# Wallboxsteuerung-WEMOS-14062021.net
KiCad netlist of a schematic drawn in EAGLE
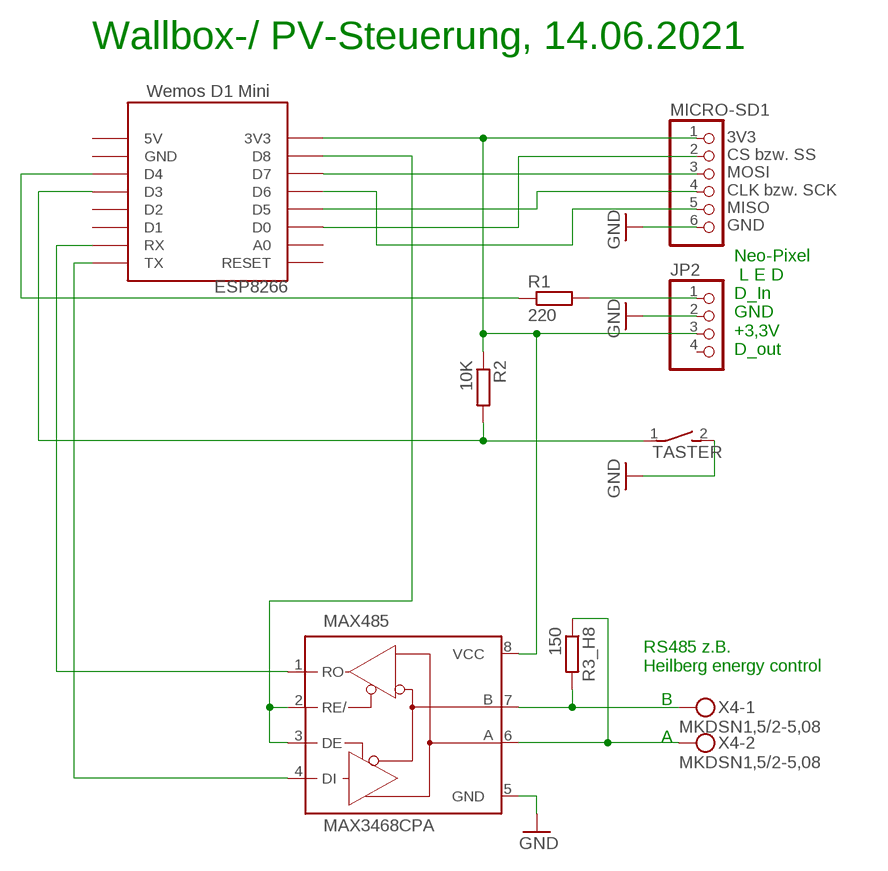
[diagram p0: schematic, sheet 1]

(export (version "E")
  (design (tool "Eeschema 10.0.6"))
  (components
    (comp (ref "ESP8266")
      (value "Wemos D1 Mini")
      (footprint "eagle-import:WEMOS-D1-MINI")
      (libsource (lib "eagle-import") (part "WEMOS-D1-MINI"))
    )
    (comp (ref "JP2")
      (value "PINHD-1X4")
      (footprint "eagle-import:1X04")
      (libsource (lib "eagle-import") (part "PINHD-1X4"))
    )
    (comp (ref "MAX485")
      (value "MAX3468CPA")
      (footprint "eagle-import:DIL08")
      (libsource (lib "eagle-import") (part "MAX34PA68C"))
    )
    (comp (ref "MICRO-SD1")
      (value "PINHD-1X6")
      (footprint "eagle-import:1X06")
      (libsource (lib "eagle-import") (part "PINHD-1X6"))
    )
    (comp (ref "R1")
      (value "220")
      (footprint "eagle-import:0309V")
      (libsource (lib "eagle-import") (part "R-EU_0309/V"))
    )
    (comp (ref "R2")
      (value "10K")
      (footprint "eagle-import:0309V")
      (libsource (lib "eagle-import") (part "R-EU_0309/V"))
    )
    (comp (ref "R3_H8")
      (value "150")
      (footprint "eagle-import:0309V")
      (libsource (lib "eagle-import") (part "R-EU_0309/V"))
    )
    (comp (ref "TASTER")
      (value "DS01E")
      (footprint "eagle-import:DS-01")
      (libsource (lib "eagle-import") (part "DS01E"))
    )
    (comp (ref "X4")
      (value "MKDSN1,5/2-5,08")
      (footprint "eagle-import:MKDSN1,5_2-5,08")
      (libsource (lib "eagle-import") (part "MKDSN1,5/2-5,08"))
    )
  )
  (nets
    (net (code "1") (name "GND") (class "Default")
      (node (ref "JP2") (pin "2") (pinfunction "2_2") (pintype "passive"))
      (node (ref "MAX485") (pin "5") (pinfunction "GND_5") (pintype "power_in"))
      (node (ref "MICRO-SD1") (pin "6") (pinfunction "6_6") (pintype "passive"))
      (node (ref "TASTER") (pin "2") (pinfunction "2_2") (pintype "passive"))
    )
    (net (code "2") (name "Net-(ESP8266-PadD0)") (class "Default")
      (node (ref "ESP8266") (pin "D0") (pinfunction "D0_D0") (pintype "bidirectional"))
      (node (ref "MICRO-SD1") (pin "2") (pinfunction "2_2") (pintype "passive"))
    )
    (net (code "3") (name "Net-(ESP8266-PadD3)") (class "Default")
      (node (ref "ESP8266") (pin "D3") (pinfunction "D3_D3") (pintype "bidirectional"))
      (node (ref "R2") (pin "2") (pinfunction "2_2") (pintype "passive"))
      (node (ref "TASTER") (pin "1") (pinfunction "1_1") (pintype "passive"))
    )
    (net (code "4") (name "Net-(ESP8266-PadD4)") (class "Default")
      (node (ref "ESP8266") (pin "D4") (pinfunction "D4_D4") (pintype "bidirectional"))
      (node (ref "R1") (pin "1") (pinfunction "1_1") (pintype "passive"))
    )
    (net (code "5") (name "Net-(ESP8266-PadD5)") (class "Default")
      (node (ref "ESP8266") (pin "D5") (pinfunction "D5_D5") (pintype "bidirectional"))
      (node (ref "MICRO-SD1") (pin "4") (pinfunction "4_4") (pintype "passive"))
    )
    (net (code "6") (name "Net-(ESP8266-PadD6)") (class "Default")
      (node (ref "ESP8266") (pin "D6") (pinfunction "D6_D6") (pintype "bidirectional"))
      (node (ref "MICRO-SD1") (pin "5") (pinfunction "5_5") (pintype "passive"))
    )
    (net (code "7") (name "Net-(ESP8266-PadD7)") (class "Default")
      (node (ref "ESP8266") (pin "D7") (pinfunction "D7_D7") (pintype "bidirectional"))
      (node (ref "MICRO-SD1") (pin "3") (pinfunction "3_3") (pintype "passive"))
    )
    (net (code "8") (name "Net-(JP2-Pad1)") (class "Default")
      (node (ref "JP2") (pin "1") (pinfunction "1_1") (pintype "passive"))
      (node (ref "R1") (pin "2") (pinfunction "2_2") (pintype "passive"))
    )
    (net (code "9") (name "Net-(MAX485-A)") (class "Default")
      (node (ref "MAX485") (pin "6") (pinfunction "A_6") (pintype "passive"))
      (node (ref "R3_H8") (pin "1") (pinfunction "1_1") (pintype "passive"))
      (node (ref "X4") (pin "2") (pinfunction "KL_2") (pintype "passive"))
    )
    (net (code "10") (name "Net-(MAX485-B)") (class "Default")
      (node (ref "MAX485") (pin "7") (pinfunction "B_7") (pintype "passive"))
      (node (ref "R3_H8") (pin "2") (pinfunction "2_2") (pintype "passive"))
      (node (ref "X4") (pin "1") (pinfunction "KL_1") (pintype "passive"))
    )
    (net (code "11") (name "Net-(MAX485-DE)") (class "Default")
      (node (ref "ESP8266") (pin "D8") (pinfunction "D8_D8") (pintype "bidirectional"))
      (node (ref "MAX485") (pin "2") (pinfunction "RE/_2") (pintype "input"))
      (node (ref "MAX485") (pin "3") (pinfunction "DE_3") (pintype "input"))
    )
    (net (code "12") (name "Net-(MAX485-DI)") (class "Default")
      (node (ref "ESP8266") (pin "TX") (pinfunction "TX_TX") (pintype "bidirectional"))
      (node (ref "MAX485") (pin "4") (pinfunction "DI_4") (pintype "input"))
    )
    (net (code "13") (name "Net-(MAX485-RO)") (class "Default")
      (node (ref "ESP8266") (pin "RX") (pinfunction "RX_RX") (pintype "bidirectional"))
      (node (ref "MAX485") (pin "1") (pinfunction "RO_1") (pintype "output"))
    )
    (net (code "14") (name "Net-(MAX485-VCC)") (class "Default")
      (node (ref "ESP8266") (pin "3V3") (pinfunction "3V3_3V3") (pintype "bidirectional"))
      (node (ref "JP2") (pin "3") (pinfunction "3_3") (pintype "passive"))
      (node (ref "MAX485") (pin "8") (pinfunction "VCC_8") (pintype "power_in"))
      (node (ref "MICRO-SD1") (pin "1") (pinfunction "1_1") (pintype "passive"))
      (node (ref "R2") (pin "1") (pinfunction "1_1") (pintype "passive"))
    )
    (net (code "15") (name "unconnected-(ESP8266-Pad5V)") (class "Default")
      (node (ref "ESP8266") (pin "5V") (pinfunction "5V_5V") (pintype "bidirectional"))
    )
    (net (code "16") (name "unconnected-(ESP8266-PadA0)") (class "Default")
      (node (ref "ESP8266") (pin "A0") (pinfunction "A0_A0") (pintype "bidirectional"))
    )
    (net (code "17") (name "unconnected-(ESP8266-PadD1)") (class "Default")
      (node (ref "ESP8266") (pin "D1") (pinfunction "D1_D1") (pintype "bidirectional"))
    )
    (net (code "18") (name "unconnected-(ESP8266-PadD2)") (class "Default")
      (node (ref "ESP8266") (pin "D2") (pinfunction "D2_D2") (pintype "bidirectional"))
    )
    (net (code "19") (name "unconnected-(ESP8266-PadGND)") (class "Default")
      (node (ref "ESP8266") (pin "GND") (pinfunction "GND_GND") (pintype "bidirectional"))
    )
    (net (code "20") (name "unconnected-(ESP8266-PadRESET)") (class "Default")
      (node (ref "ESP8266") (pin "RESET") (pinfunction "RESET_RESET") (pintype "bidirectional"))
    )
    (net (code "21") (name "unconnected-(JP2-Pad4)") (class "Default")
      (node (ref "JP2") (pin "4") (pinfunction "4_4") (pintype "passive"))
    )
  )
)
